# PI_Shield.net
KiCad netlist of a schematic drawn in EAGLE
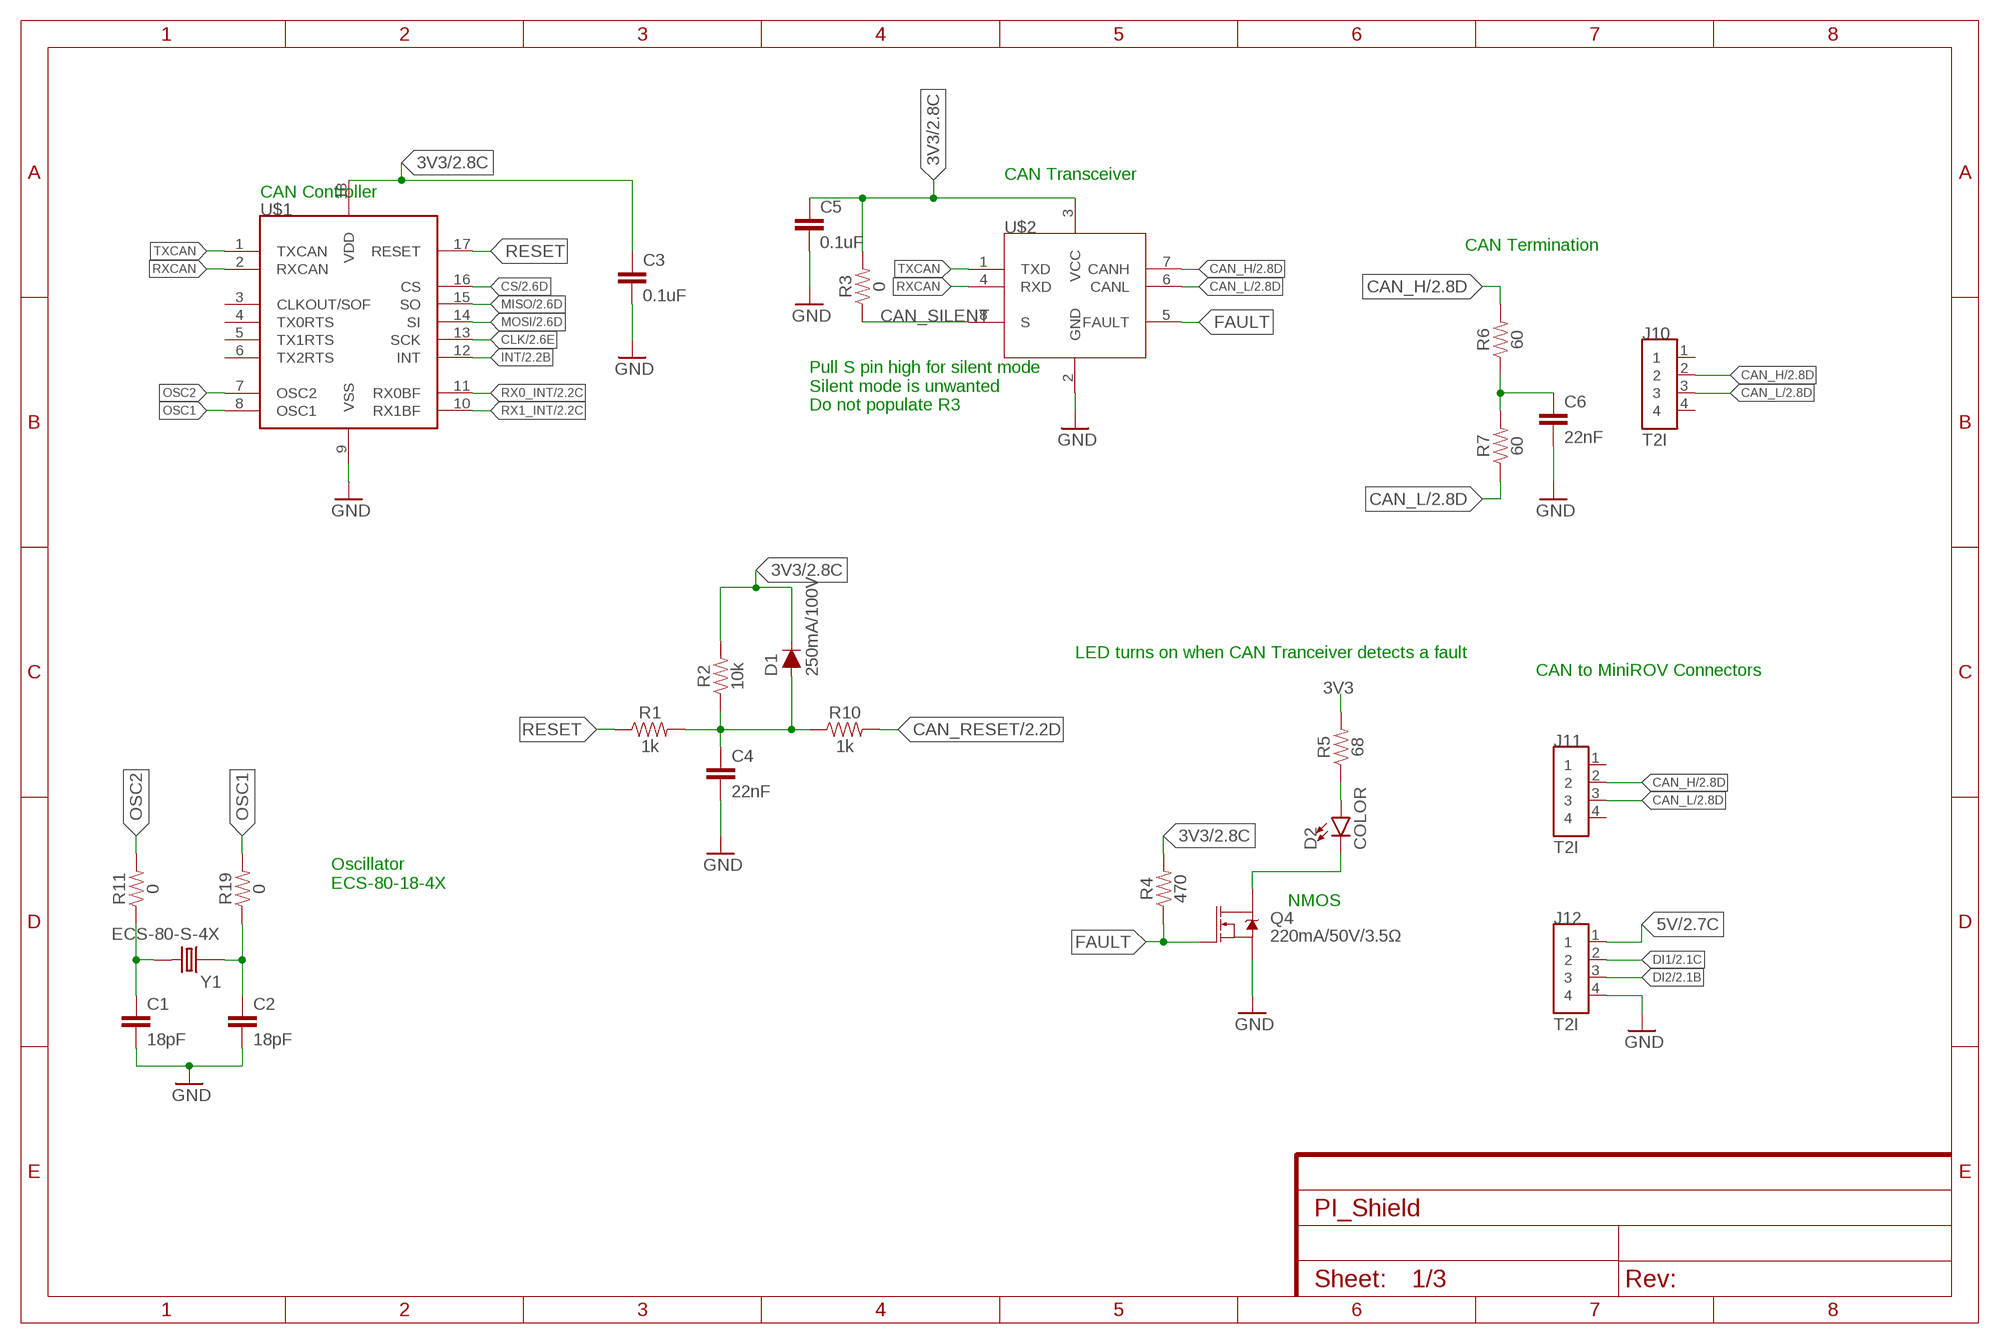
[diagram p0: schematic, sheet 1]
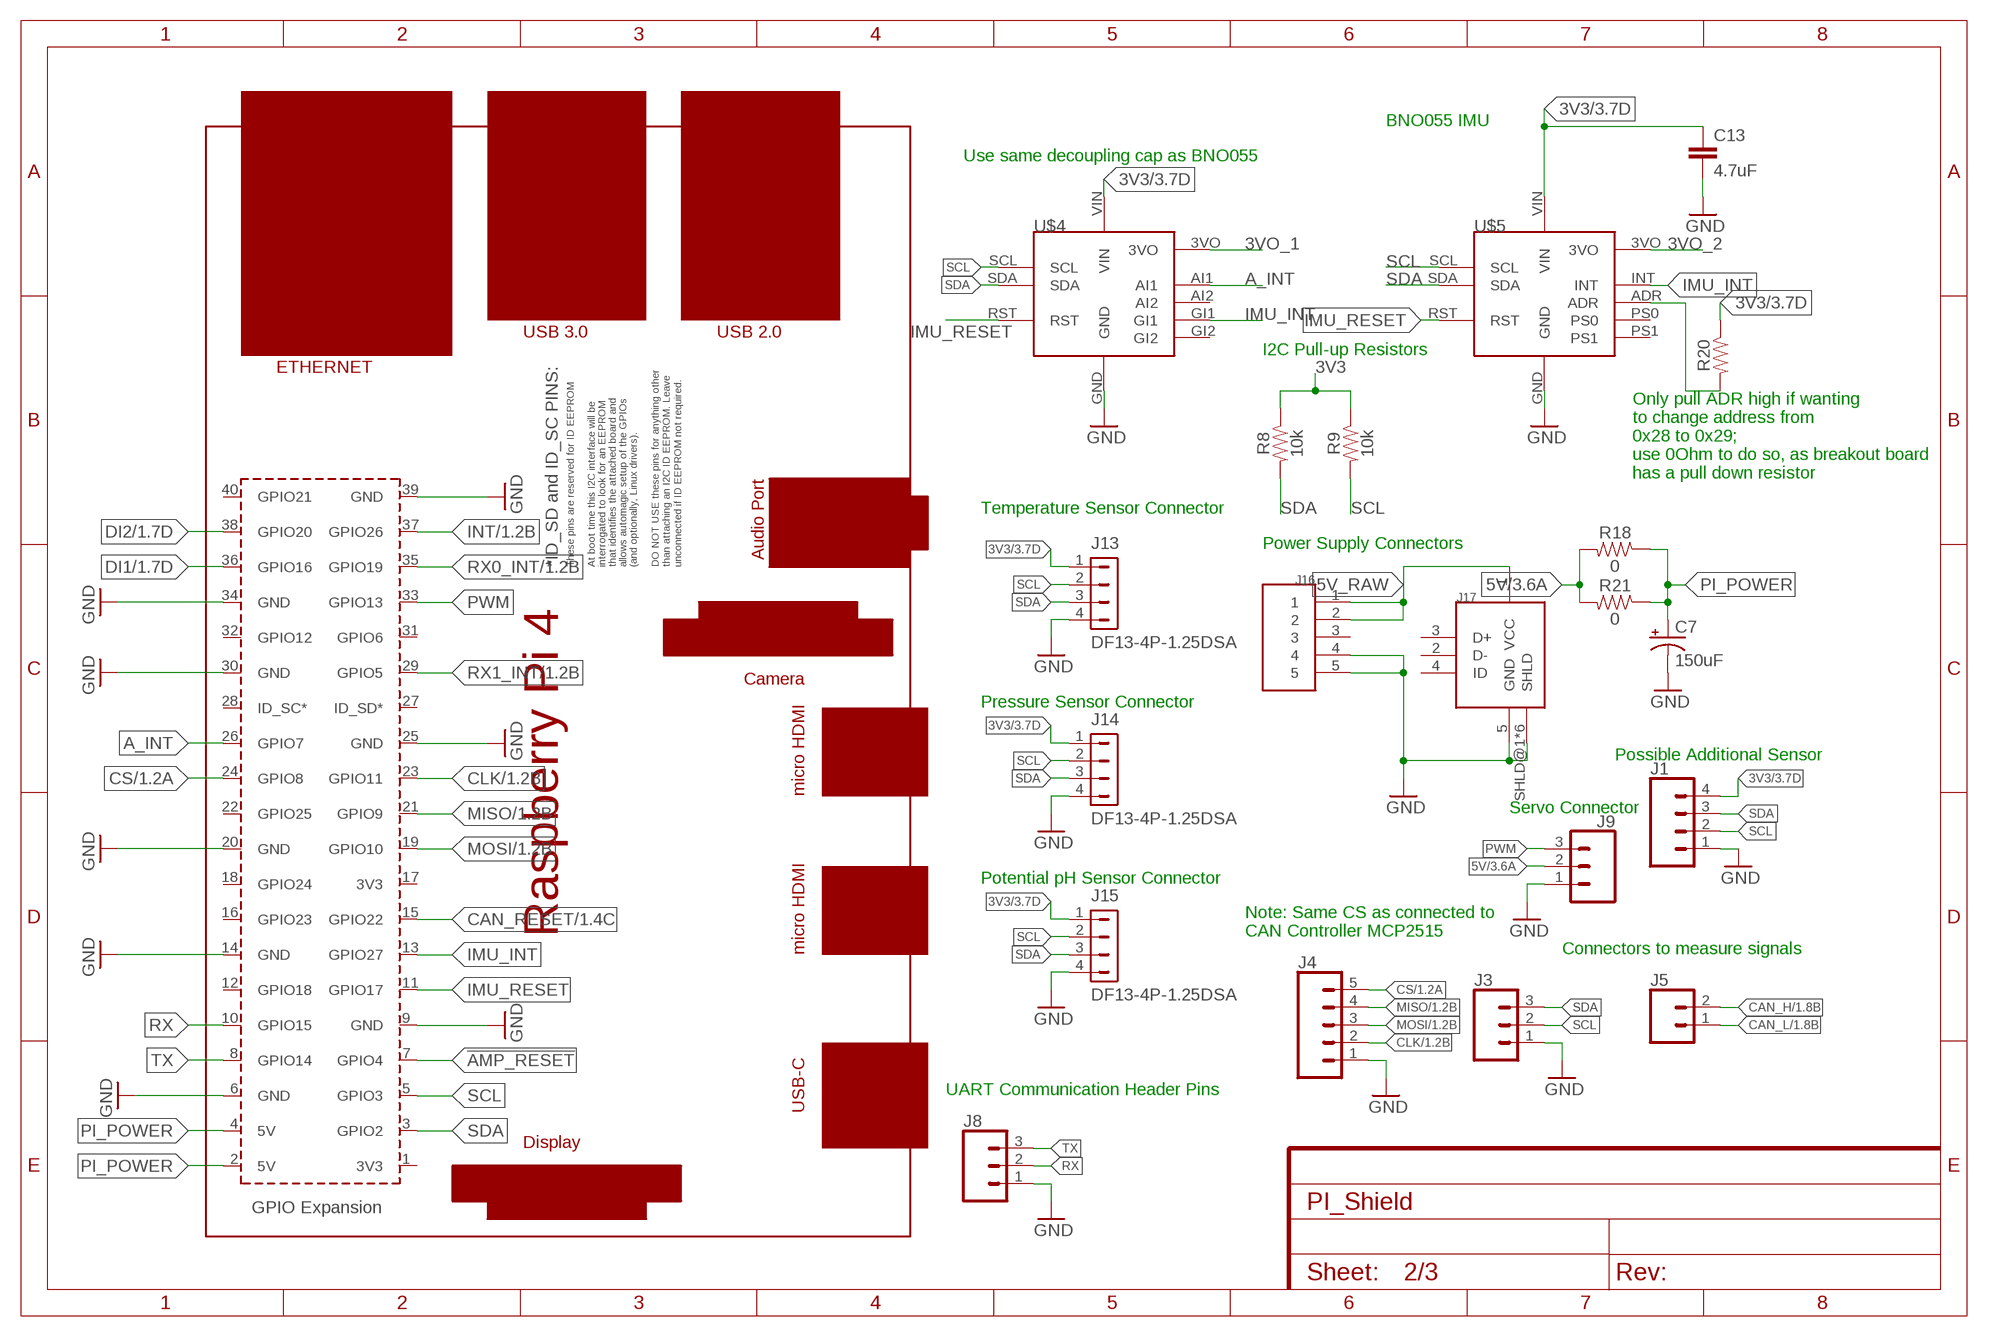
[diagram p1: schematic, sheet 2]
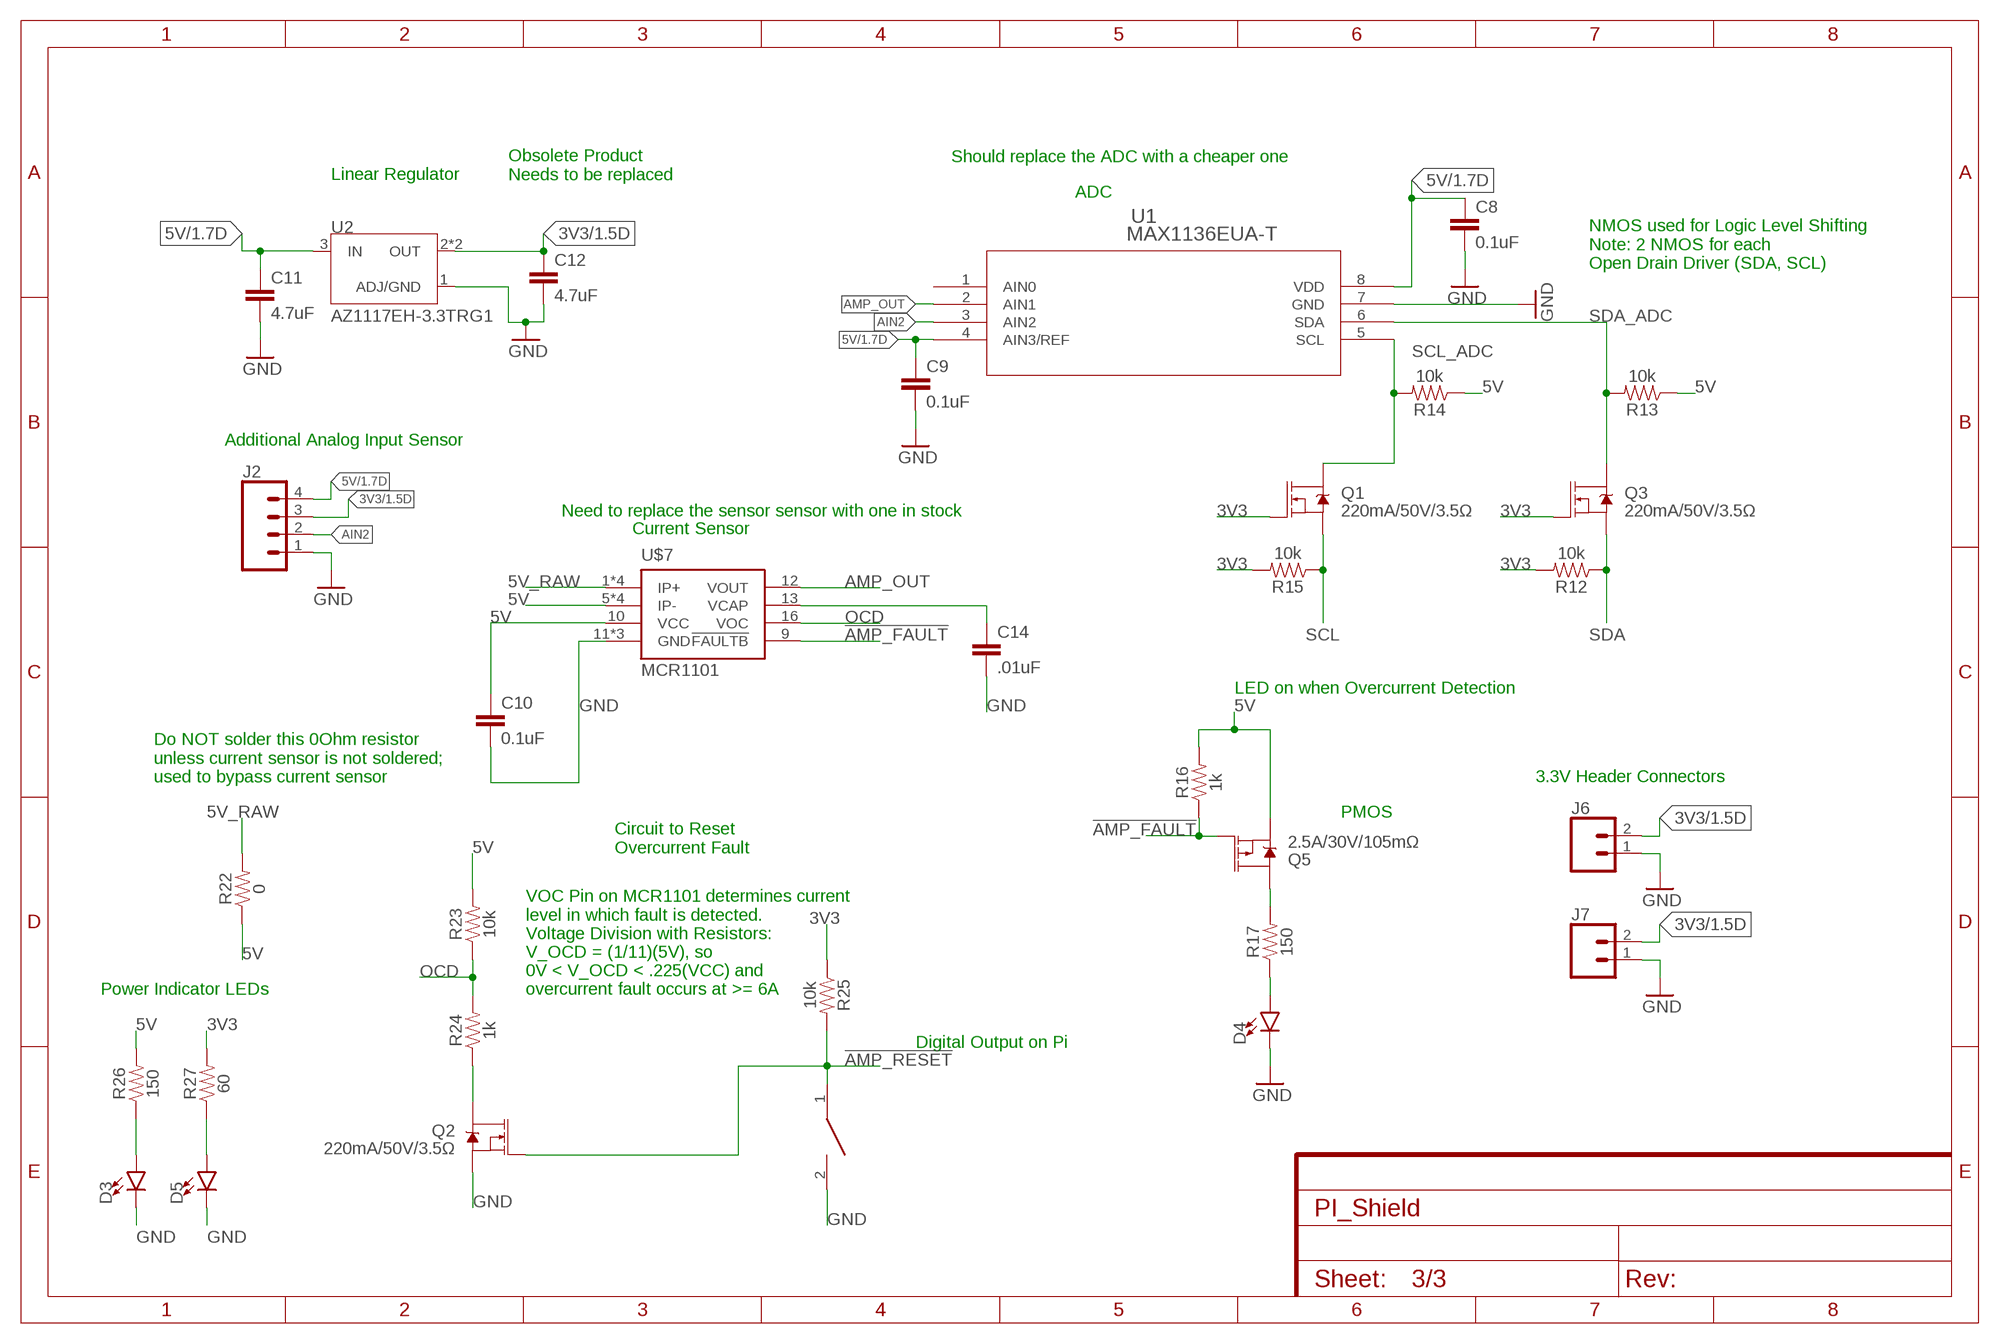
[diagram p2: schematic, sheet 3]

(export (version "E")
  (design (tool "Eeschema 10.0.6"))
  (components
    (comp (ref "C1")
      (value "18pF")
      (footprint "eagle-import:0603")
      (libsource (lib "eagle-import") (part "18PF-0603-50V-5%"))
    )
    (comp (ref "C2")
      (value "18pF")
      (footprint "eagle-import:0603")
      (libsource (lib "eagle-import") (part "18PF-0603-50V-5%"))
    )
    (comp (ref "C3")
      (value "0.1uF")
      (footprint "eagle-import:0603")
      (libsource (lib "eagle-import") (part "22NF/22,000PF-0603-50V-10%"))
    )
    (comp (ref "C4")
      (value "22nF")
      (footprint "eagle-import:0603")
      (libsource (lib "eagle-import") (part "22NF/22,000PF-0603-50V-10%"))
    )
    (comp (ref "C5")
      (value "0.1uF")
      (footprint "eagle-import:0603")
      (libsource (lib "eagle-import") (part "22NF/22,000PF-0603-50V-10%"))
    )
    (comp (ref "C6")
      (value "22nF")
      (footprint "eagle-import:0603")
      (libsource (lib "eagle-import") (part "22NF/22,000PF-0603-50V-10%"))
    )
    (comp (ref "D1")
      (value "250mA/100V")
      (footprint "eagle-import:SOD-323")
      (libsource (lib "eagle-import") (part "DIODE-BAS16J"))
    )
    (comp (ref "D2")
      (value "COLOR")
      (footprint "eagle-import:0805")
      (libsource (lib "eagle-import") (part "LED-0805"))
    )
    (comp (ref "J10")
      (value "T2I")
      (footprint "eagle-import:T2I")
      (libsource (lib "eagle-import") (part "T2I"))
    )
    (comp (ref "J11")
      (value "T2I")
      (footprint "eagle-import:T2I")
      (libsource (lib "eagle-import") (part "T2I"))
    )
    (comp (ref "J12")
      (value "T2I")
      (footprint "eagle-import:T2I")
      (libsource (lib "eagle-import") (part "T2I"))
    )
    (comp (ref "Q4")
      (value "220mA/50V/3.5Ω")
      (footprint "eagle-import:SOT23-3")
      (libsource (lib "eagle-import") (part "MOSFET-NCH-BSS138"))
    )
    (comp (ref "R1")
      (value "1k")
      (footprint "eagle-import:0603")
      (libsource (lib "eagle-import") (part "RESISTOR0603"))
    )
    (comp (ref "R2")
      (value "10k")
      (footprint "eagle-import:0603")
      (libsource (lib "eagle-import") (part "RESISTOR0603"))
    )
    (comp (ref "R3")
      (value "0")
      (footprint "eagle-import:0603")
      (libsource (lib "eagle-import") (part "RESISTOR0603"))
    )
    (comp (ref "R4")
      (value "470")
      (footprint "eagle-import:0603")
      (libsource (lib "eagle-import") (part "RESISTOR0603"))
    )
    (comp (ref "R5")
      (value "68")
      (footprint "eagle-import:0603")
      (libsource (lib "eagle-import") (part "RESISTOR0603"))
    )
    (comp (ref "R6")
      (value "60")
      (footprint "eagle-import:0603")
      (libsource (lib "eagle-import") (part "RESISTOR0603"))
    )
    (comp (ref "R7")
      (value "60")
      (footprint "eagle-import:0603")
      (libsource (lib "eagle-import") (part "RESISTOR0603"))
    )
    (comp (ref "R10")
      (value "1k")
      (footprint "eagle-import:0603")
      (libsource (lib "eagle-import") (part "RESISTOR0603"))
    )
    (comp (ref "R11")
      (value "0")
      (footprint "eagle-import:0603")
      (libsource (lib "eagle-import") (part "RESISTOR0603"))
    )
    (comp (ref "R19")
      (value "0")
      (footprint "eagle-import:0603")
      (libsource (lib "eagle-import") (part "RESISTOR0603"))
    )
    (comp (ref "U$1")
      (value "MCP2515")
      (footprint "eagle-import:SOIC-18")
      (libsource (lib "eagle-import") (part "MCP2515"))
    )
    (comp (ref "U$2")
      (value "TCAN337D")
      (footprint "eagle-import:SOIC-8")
      (libsource (lib "eagle-import") (part "TCAN337D"))
    )
    (comp (ref "Y1")
      (value "ECS-80-S-4X")
      (footprint "eagle-import:XTAL_ECS-80-S-4X")
      (fields (field (name "DIGI-KEY_PART_NUMBER") "X1057-ND") (field (name "MF") "ECS International"))
      (libsource (lib "eagle-import") (part "ECS-80-S-4X"))
    )
    (comp (ref "C8")
      (value "0.1uF")
      (footprint "eagle-import:0603")
      (libsource (lib "eagle-import") (part "22NF/22,000PF-0603-50V-10%"))
    )
    (comp (ref "C9")
      (value "0.1uF")
      (footprint "eagle-import:0603")
      (libsource (lib "eagle-import") (part "22NF/22,000PF-0603-50V-10%"))
    )
    (comp (ref "C10")
      (value "0.1uF")
      (footprint "eagle-import:0603")
      (libsource (lib "eagle-import") (part "22NF/22,000PF-0603-50V-10%"))
    )
    (comp (ref "C11")
      (value "4.7uF")
      (footprint "eagle-import:0603")
      (libsource (lib "eagle-import") (part "22NF/22,000PF-0603-50V-10%"))
    )
    (comp (ref "C12")
      (value "4.7uF")
      (footprint "eagle-import:0603")
      (libsource (lib "eagle-import") (part "22NF/22,000PF-0603-50V-10%"))
    )
    (comp (ref "C14")
      (value ".01uF")
      (footprint "eagle-import:0603")
      (libsource (lib "eagle-import") (part "22NF/22,000PF-0603-50V-10%"))
    )
    (comp (ref "D3")
      (value "LED0603")
      (footprint "eagle-import:LED-0603")
      (libsource (lib "eagle-import") (part "LED0603"))
    )
    (comp (ref "D4")
      (value "LED0603")
      (footprint "eagle-import:LED-0603")
      (libsource (lib "eagle-import") (part "LED0603"))
    )
    (comp (ref "D5")
      (value "LED0603")
      (footprint "eagle-import:LED-0603")
      (libsource (lib "eagle-import") (part "LED0603"))
    )
    (comp (ref "J2")
      (value "CONN_04")
      (footprint "eagle-import:1X04")
      (libsource (lib "eagle-import") (part "CONN_04"))
    )
    (comp (ref "J6")
      (value "CONN_02")
      (footprint "eagle-import:1X02")
      (libsource (lib "eagle-import") (part "CONN_02"))
    )
    (comp (ref "J7")
      (value "CONN_02")
      (footprint "eagle-import:1X02")
      (libsource (lib "eagle-import") (part "CONN_02"))
    )
    (comp (ref "Q1")
      (value "220mA/50V/3.5Ω")
      (footprint "eagle-import:SOT23-3")
      (libsource (lib "eagle-import") (part "MOSFET-NCH-BSS138"))
    )
    (comp (ref "Q2")
      (value "220mA/50V/3.5Ω")
      (footprint "eagle-import:SOT23-3")
      (libsource (lib "eagle-import") (part "MOSFET-NCH-BSS138"))
    )
    (comp (ref "Q3")
      (value "220mA/50V/3.5Ω")
      (footprint "eagle-import:SOT23-3")
      (libsource (lib "eagle-import") (part "MOSFET-NCH-BSS138"))
    )
    (comp (ref "Q5")
      (value "2.5A/30V/105mΩ")
      (footprint "eagle-import:SOT23-3")
      (libsource (lib "eagle-import") (part "MOSFET_PCH-DMG2307L"))
    )
    (comp (ref "R12")
      (value "10k")
      (footprint "eagle-import:0603")
      (libsource (lib "eagle-import") (part "RESISTOR0603"))
    )
    (comp (ref "R13")
      (value "10k")
      (footprint "eagle-import:0603")
      (libsource (lib "eagle-import") (part "RESISTOR0603"))
    )
    (comp (ref "R14")
      (value "10k")
      (footprint "eagle-import:0603")
      (libsource (lib "eagle-import") (part "RESISTOR0603"))
    )
    (comp (ref "R15")
      (value "10k")
      (footprint "eagle-import:0603")
      (libsource (lib "eagle-import") (part "RESISTOR0603"))
    )
    (comp (ref "R16")
      (value "1k")
      (footprint "eagle-import:0603")
      (libsource (lib "eagle-import") (part "RESISTOR0603"))
    )
    (comp (ref "R17")
      (value "150")
      (footprint "eagle-import:0603")
      (libsource (lib "eagle-import") (part "RESISTOR0603"))
    )
    (comp (ref "R22")
      (value "0")
      (footprint "eagle-import:0603")
      (libsource (lib "eagle-import") (part "RESISTOR0603"))
    )
    (comp (ref "R23")
      (value "10k")
      (footprint "eagle-import:0603")
      (libsource (lib "eagle-import") (part "RESISTOR0603"))
    )
    (comp (ref "R24")
      (value "1k")
      (footprint "eagle-import:0603")
      (libsource (lib "eagle-import") (part "RESISTOR0603"))
    )
    (comp (ref "R25")
      (value "10k")
      (footprint "eagle-import:0603")
      (libsource (lib "eagle-import") (part "RESISTOR0603"))
    )
    (comp (ref "R26")
      (value "150")
      (footprint "eagle-import:0603")
      (libsource (lib "eagle-import") (part "RESISTOR0603"))
    )
    (comp (ref "R27")
      (value "60")
      (footprint "eagle-import:0603")
      (libsource (lib "eagle-import") (part "RESISTOR0603"))
    )
    (comp (ref "U$6")
      (value "DISCRETECOMPONENTS_SWITCH")
      (footprint "eagle-import:DISCRETECOMPONENTS_SW_2512")
      (libsource (lib "eagle-import") (part "DISCRETECOMPONENTS_SWITCH"))
    )
    (comp (ref "U$7")
      (value "MCR1101")
      (footprint "eagle-import:SOIC-16")
      (libsource (lib "eagle-import") (part "MCR1101"))
    )
    (comp (ref "U1")
      (value "MAX1136EUA-T")
      (footprint "eagle-import:21-0036K")
      (fields
        (field (name "DIGI-KEY_PART_NUMBER") "MAX1136EUA+-ND")
        (field (name "MF") "Maxim Integrated")
        (field (name "MP") "MAX1136EUA+")
      )
      (libsource (lib "eagle-import") (part "MAX1136EUA-T"))
    )
    (comp (ref "U2")
      (value "AZ1117EH-3.3TRG1")
      (footprint "eagle-import:SOT230P700X180-4N")
      (fields (field (name "MF") "Diodes Inc."))
      (libsource (lib "eagle-import") (part "AZ1117EH-3.3TRG1"))
    )
    (comp (ref "C7")
      (value "150uF")
      (footprint "eagle-import:2917(7343-31-METRIC)")
      (libsource (lib "eagle-import") (part "C-TANTALUM(10UF_150UF)"))
    )
    (comp (ref "C13")
      (value "4.7uF")
      (footprint "eagle-import:0603")
      (libsource (lib "eagle-import") (part "22NF/22,000PF-0603-50V-10%"))
    )
    (comp (ref "J1")
      (value "CONN_04")
      (footprint "eagle-import:1X04")
      (libsource (lib "eagle-import") (part "CONN_04"))
    )
    (comp (ref "J3")
      (value "CONN_03")
      (footprint "eagle-import:1X03")
      (libsource (lib "eagle-import") (part "CONN_03"))
    )
    (comp (ref "J4")
      (value "CONN_05")
      (footprint "eagle-import:1X05")
      (libsource (lib "eagle-import") (part "CONN_05"))
    )
    (comp (ref "J5")
      (value "CONN_02")
      (footprint "eagle-import:1X02")
      (libsource (lib "eagle-import") (part "SparkFun-Connectors_513_CONN_02"))
    )
    (comp (ref "J8")
      (value "CONN_03")
      (footprint "eagle-import:1X03")
      (libsource (lib "eagle-import") (part "CONN_03"))
    )
    (comp (ref "J9")
      (value "CONN_03")
      (footprint "eagle-import:1X03")
      (libsource (lib "eagle-import") (part "CONN_03"))
    )
    (comp (ref "J13")
      (value "DF13-4P-1.25DSA")
      (footprint "eagle-import:DF13-4P-1.25DSA")
      (libsource (lib "eagle-import") (part "DF13-4P-1.25DSA"))
    )
    (comp (ref "J14")
      (value "DF13-4P-1.25DSA")
      (footprint "eagle-import:DF13-4P-1.25DSA")
      (libsource (lib "eagle-import") (part "DF13-4P-1.25DSA"))
    )
    (comp (ref "J15")
      (value "DF13-4P-1.25DSA")
      (footprint "eagle-import:DF13-4P-1.25DSA")
      (libsource (lib "eagle-import") (part "DF13-4P-1.25DSA"))
    )
    (comp (ref "J16")
      (value "T2I5P")
      (footprint "eagle-import:T2I5P")
      (libsource (lib "eagle-import") (part "T2I5P"))
    )
    (comp (ref "J17")
      (value "USB-MICRO")
      (footprint "eagle-import:MICRO-USB")
      (libsource (lib "eagle-import") (part "USB-MICRO"))
    )
    (comp (ref "R8")
      (value "10k")
      (footprint "eagle-import:0603")
      (libsource (lib "eagle-import") (part "RESISTOR0603"))
    )
    (comp (ref "R9")
      (value "10k")
      (footprint "eagle-import:0603")
      (libsource (lib "eagle-import") (part "RESISTOR0603"))
    )
    (comp (ref "R18")
      (value "0")
      (footprint "eagle-import:0603")
      (libsource (lib "eagle-import") (part "RESISTOR0603"))
    )
    (comp (ref "R20")
      (value "RESISTOR0603")
      (footprint "eagle-import:0603")
      (libsource (lib "eagle-import") (part "RESISTOR0603"))
    )
    (comp (ref "R21")
      (value "0")
      (footprint "eagle-import:0603")
      (libsource (lib "eagle-import") (part "RESISTOR0603"))
    )
    (comp (ref "U$4")
      (value "ADAFRUIT-FXOS8700-FXAS21002")
      (footprint "eagle-import:ADAFRUIT-FXOS8700-FXAS21002")
      (libsource (lib "eagle-import") (part "ADAFRUIT-FXOS8700-FXAS21002"))
    )
    (comp (ref "U$5")
      (value "ADAFRUIT-BNO055")
      (footprint "eagle-import:ADAFRUIT-BNO055")
      (libsource (lib "eagle-import") (part "ADAFRUIT-BNO055"))
    )
    (comp (ref "U$8")
      (value "RPI4")
      (footprint "eagle-import:RPI4")
      (libsource (lib "eagle-import") (part "RPI4"))
    )
  )
  (nets
    (net (code "1") (name "3V3") (class "Default")
      (node (ref "C12") (pin "1") (pinfunction "1_1") (pintype "passive"))
      (node (ref "C13") (pin "1") (pinfunction "1_1") (pintype "passive"))
      (node (ref "C3") (pin "1") (pinfunction "1_1") (pintype "passive"))
      (node (ref "C5") (pin "1") (pinfunction "1_1") (pintype "passive"))
      (node (ref "D1") (pin "C") (pinfunction "C_C") (pintype "passive"))
      (node (ref "J1") (pin "4") (pinfunction "4_4") (pintype "passive"))
      (node (ref "J13") (pin "1") (pinfunction "1_1") (pintype "passive"))
      (node (ref "J14") (pin "1") (pinfunction "1_1") (pintype "passive"))
      (node (ref "J15") (pin "1") (pinfunction "1_1") (pintype "passive"))
      (node (ref "J2") (pin "3") (pinfunction "3_3") (pintype "passive"))
      (node (ref "J6") (pin "2") (pinfunction "2_2") (pintype "passive"))
      (node (ref "J7") (pin "2") (pinfunction "2_2") (pintype "passive"))
      (node (ref "Q1") (pin "1") (pinfunction "G_1") (pintype "bidirectional"))
      (node (ref "Q3") (pin "1") (pinfunction "G_1") (pintype "bidirectional"))
      (node (ref "R12") (pin "2") (pinfunction "2_2") (pintype "passive"))
      (node (ref "R15") (pin "2") (pinfunction "2_2") (pintype "passive"))
      (node (ref "R2") (pin "2") (pinfunction "2_2") (pintype "passive"))
      (node (ref "R20") (pin "1") (pinfunction "1_1") (pintype "passive"))
      (node (ref "R25") (pin "1") (pinfunction "1_1") (pintype "passive"))
      (node (ref "R27") (pin "2") (pinfunction "2_2") (pintype "passive"))
      (node (ref "R3") (pin "2") (pinfunction "2_2") (pintype "passive"))
      (node (ref "R4") (pin "2") (pinfunction "2_2") (pintype "passive"))
      (node (ref "R5") (pin "2") (pinfunction "2_2") (pintype "passive"))
      (node (ref "R8") (pin "1") (pinfunction "1_1") (pintype "passive"))
      (node (ref "R9") (pin "1") (pinfunction "1_1") (pintype "passive"))
      (node (ref "U$1") (pin "18") (pinfunction "VDD_18") (pintype "bidirectional"))
      (node (ref "U$2") (pin "3") (pinfunction "VCC_3") (pintype "bidirectional"))
      (node (ref "U$4") (pin "VIN") (pinfunction "VIN_VIN") (pintype "power_in"))
      (node (ref "U$5") (pin "VIN") (pinfunction "VIN_VIN") (pintype "power_in"))
      (node (ref "U2") (pin "2") (pinfunction "OUT_2") (pintype "output"))
      (node (ref "U2") (pin "4") (pinfunction "OUT_4") (pintype "output"))
    )
    (net (code "2") (name "3VO_1") (class "Default")
      (node (ref "U$4") (pin "3VO") (pinfunction "3VO_3VO") (pintype "power_in"))
    )
    (net (code "3") (name "3VO_2") (class "Default")
      (node (ref "U$5") (pin "3VO") (pinfunction "3VO_3VO") (pintype "power_in"))
    )
    (net (code "4") (name "5V") (class "Default")
      (node (ref "C10") (pin "1") (pinfunction "1_1") (pintype "passive"))
      (node (ref "C11") (pin "1") (pinfunction "1_1") (pintype "passive"))
      (node (ref "C8") (pin "1") (pinfunction "1_1") (pintype "passive"))
      (node (ref "C9") (pin "1") (pinfunction "1_1") (pintype "passive"))
      (node (ref "J12") (pin "1") (pinfunction "1_1") (pintype "bidirectional"))
      (node (ref "J2") (pin "4") (pinfunction "4_4") (pintype "passive"))
      (node (ref "J9") (pin "2") (pinfunction "2_2") (pintype "passive"))
      (node (ref "Q5") (pin "2") (pinfunction "S_2") (pintype "bidirectional"))
      (node (ref "R13") (pin "1") (pinfunction "1_1") (pintype "passive"))
      (node (ref "R14") (pin "1") (pinfunction "1_1") (pintype "passive"))
      (node (ref "R16") (pin "2") (pinfunction "2_2") (pintype "passive"))
      (node (ref "R18") (pin "2") (pinfunction "2_2") (pintype "passive"))
      (node (ref "R21") (pin "2") (pinfunction "2_2") (pintype "passive"))
      (node (ref "R22") (pin "1") (pinfunction "1_1") (pintype "passive"))
      (node (ref "R23") (pin "2") (pinfunction "2_2") (pintype "passive"))
      (node (ref "R26") (pin "2") (pinfunction "2_2") (pintype "passive"))
      (node (ref "U$7") (pin "10") (pinfunction "VCC_10") (pintype "bidirectional"))
      (node (ref "U$7") (pin "5") (pinfunction "IP-_5") (pintype "bidirectional"))
      (node (ref "U$7") (pin "6") (pinfunction "IP-_6") (pintype "bidirectional"))
      (node (ref "U$7") (pin "7") (pinfunction "IP-_7") (pintype "bidirectional"))
      (node (ref "U$7") (pin "8") (pinfunction "IP-_8") (pintype "bidirectional"))
      (node (ref "U1") (pin "4") (pinfunction "AIN3/REF_4") (pintype "bidirectional"))
      (node (ref "U1") (pin "8") (pinfunction "VDD_8") (pintype "power_in"))
      (node (ref "U2") (pin "3") (pinfunction "IN_3") (pintype "input"))
    )
    (net (code "5") (name "5V_RAW") (class "Default")
      (node (ref "J16") (pin "1") (pinfunction "1_1") (pintype "bidirectional"))
      (node (ref "J16") (pin "2") (pinfunction "2_2") (pintype "bidirectional"))
      (node (ref "J17") (pin "1") (pinfunction "VCC_1") (pintype "bidirectional"))
      (node (ref "R22") (pin "2") (pinfunction "2_2") (pintype "passive"))
      (node (ref "U$7") (pin "1") (pinfunction "IP+_1") (pintype "bidirectional"))
      (node (ref "U$7") (pin "2") (pinfunction "IP+_2") (pintype "bidirectional"))
      (node (ref "U$7") (pin "3") (pinfunction "IP+_3") (pintype "bidirectional"))
      (node (ref "U$7") (pin "4") (pinfunction "IP+_4") (pintype "bidirectional"))
    )
    (net (code "6") (name "AIN2") (class "Default")
      (node (ref "J2") (pin "2") (pinfunction "2_2") (pintype "passive"))
      (node (ref "U1") (pin "3") (pinfunction "AIN2_3") (pintype "bidirectional"))
    )
    (net (code "7") (name "AMP_OUT") (class "Default")
      (node (ref "U$7") (pin "12") (pinfunction "VOUT_12") (pintype "bidirectional"))
      (node (ref "U1") (pin "2") (pinfunction "AIN1_2") (pintype "bidirectional"))
    )
    (net (code "8") (name "A_INT") (class "Default")
      (node (ref "U$4") (pin "AI1") (pinfunction "AI1_AI1") (pintype "output"))
      (node (ref "U$8") (pin "26") (pinfunction "GPIO7_26") (pintype "bidirectional"))
    )
    (net (code "9") (name "CAN_H") (class "Default")
      (node (ref "J10") (pin "2") (pinfunction "2_2") (pintype "bidirectional"))
      (node (ref "J11") (pin "2") (pinfunction "2_2") (pintype "bidirectional"))
      (node (ref "J5") (pin "2") (pinfunction "2_2") (pintype "passive"))
      (node (ref "R6") (pin "2") (pinfunction "2_2") (pintype "passive"))
      (node (ref "U$2") (pin "7") (pinfunction "CANH_7") (pintype "bidirectional"))
    )
    (net (code "10") (name "CAN_L") (class "Default")
      (node (ref "J10") (pin "3") (pinfunction "3_3") (pintype "bidirectional"))
      (node (ref "J11") (pin "3") (pinfunction "3_3") (pintype "bidirectional"))
      (node (ref "J5") (pin "1") (pinfunction "1_1") (pintype "passive"))
      (node (ref "R7") (pin "1") (pinfunction "1_1") (pintype "passive"))
      (node (ref "U$2") (pin "6") (pinfunction "CANL_6") (pintype "bidirectional"))
    )
    (net (code "11") (name "CAN_RESET") (class "Default")
      (node (ref "R10") (pin "2") (pinfunction "2_2") (pintype "passive"))
      (node (ref "U$8") (pin "15") (pinfunction "GPIO22_15") (pintype "bidirectional"))
    )
    (net (code "12") (name "CAN_SILENT") (class "Default")
      (node (ref "R3") (pin "1") (pinfunction "1_1") (pintype "passive"))
      (node (ref "U$2") (pin "8") (pinfunction "S_8") (pintype "bidirectional"))
    )
    (net (code "13") (name "CLK") (class "Default")
      (node (ref "J4") (pin "2") (pinfunction "2_2") (pintype "passive"))
      (node (ref "U$1") (pin "13") (pinfunction "SCK_13") (pintype "bidirectional"))
      (node (ref "U$8") (pin "23") (pinfunction "GPIO11_23") (pintype "bidirectional"))
    )
    (net (code "14") (name "CS") (class "Default")
      (node (ref "J4") (pin "5") (pinfunction "5_5") (pintype "passive"))
      (node (ref "U$1") (pin "16") (pinfunction "CS_16") (pintype "bidirectional"))
      (node (ref "U$8") (pin "24") (pinfunction "GPIO8_24") (pintype "bidirectional"))
    )
    (net (code "15") (name "DI1") (class "Default")
      (node (ref "J12") (pin "2") (pinfunction "2_2") (pintype "bidirectional"))
      (node (ref "U$8") (pin "36") (pinfunction "GPIO16_36") (pintype "bidirectional"))
    )
    (net (code "16") (name "DI2") (class "Default")
      (node (ref "J12") (pin "3") (pinfunction "3_3") (pintype "bidirectional"))
      (node (ref "U$8") (pin "38") (pinfunction "GPIO20_38") (pintype "bidirectional"))
    )
    (net (code "17") (name "FAULT") (class "Default")
      (node (ref "Q4") (pin "1") (pinfunction "G_1") (pintype "bidirectional"))
      (node (ref "R4") (pin "1") (pinfunction "1_1") (pintype "passive"))
      (node (ref "U$2") (pin "5") (pinfunction "FAULT_5") (pintype "bidirectional"))
    )
    (net (code "18") (name "GND") (class "Default")
      (node (ref "C1") (pin "2") (pinfunction "2_2") (pintype "passive"))
      (node (ref "C10") (pin "2") (pinfunction "2_2") (pintype "passive"))
      (node (ref "C11") (pin "2") (pinfunction "2_2") (pintype "passive"))
      (node (ref "C12") (pin "2") (pinfunction "2_2") (pintype "passive"))
      (node (ref "C13") (pin "2") (pinfunction "2_2") (pintype "passive"))
      (node (ref "C14") (pin "2") (pinfunction "2_2") (pintype "passive"))
      (node (ref "C2") (pin "2") (pinfunction "2_2") (pintype "passive"))
      (node (ref "C3") (pin "2") (pinfunction "2_2") (pintype "passive"))
      (node (ref "C4") (pin "2") (pinfunction "2_2") (pintype "passive"))
      (node (ref "C5") (pin "2") (pinfunction "2_2") (pintype "passive"))
      (node (ref "C6") (pin "2") (pinfunction "2_2") (pintype "passive"))
      (node (ref "C7") (pin "-") (pinfunction "-_-") (pintype "passive"))
      (node (ref "C8") (pin "2") (pinfunction "2_2") (pintype "passive"))
      (node (ref "C9") (pin "2") (pinfunction "2_2") (pintype "passive"))
      (node (ref "D3") (pin "C") (pinfunction "C_C") (pintype "passive"))
      (node (ref "D4") (pin "C") (pinfunction "C_C") (pintype "passive"))
      (node (ref "D5") (pin "C") (pinfunction "C_C") (pintype "passive"))
      (node (ref "J1") (pin "1") (pinfunction "1_1") (pintype "passive"))
      (node (ref "J12") (pin "4") (pinfunction "4_4") (pintype "bidirectional"))
      (node (ref "J13") (pin "4") (pinfunction "4_4") (pintype "passive"))
      (node (ref "J14") (pin "4") (pinfunction "4_4") (pintype "passive"))
      (node (ref "J15") (pin "4") (pinfunction "4_4") (pintype "passive"))
      (node (ref "J16") (pin "4") (pinfunction "4_4") (pintype "bidirectional"))
      (node (ref "J16") (pin "5") (pinfunction "5_5") (pintype "bidirectional"))
      (node (ref "J17") (pin "5") (pinfunction "GND_5") (pintype "bidirectional"))
      (node (ref "J17") (pin "SHLD@1") (pinfunction "SHLD_SHLD@1") (pintype "bidirectional"))
      (node (ref "J17") (pin "SHLD@2") (pinfunction "SHLD_SHLD@2") (pintype "bidirectional"))
      (node (ref "J17") (pin "SHLD@3") (pinfunction "SHLD_SHLD@3") (pintype "bidirectional"))
      (node (ref "J17") (pin "SHLD@4") (pinfunction "SHLD_SHLD@4") (pintype "bidirectional"))
      (node (ref "J17") (pin "SHLD@5") (pinfunction "SHLD_SHLD@5") (pintype "bidirectional"))
      (node (ref "J17") (pin "SHLD@6") (pinfunction "SHLD_SHLD@6") (pintype "bidirectional"))
      (node (ref "J2") (pin "1") (pinfunction "1_1") (pintype "passive"))
      (node (ref "J3") (pin "1") (pinfunction "1_1") (pintype "passive"))
      (node (ref "J4") (pin "1") (pinfunction "1_1") (pintype "passive"))
      (node (ref "J6") (pin "1") (pinfunction "1_1") (pintype "passive"))
      (node (ref "J7") (pin "1") (pinfunction "1_1") (pintype "passive"))
      (node (ref "J8") (pin "1") (pinfunction "1_1") (pintype "passive"))
      (node (ref "J9") (pin "1") (pinfunction "1_1") (pintype "passive"))
      (node (ref "Q2") (pin "2") (pinfunction "S_2") (pintype "bidirectional"))
      (node (ref "Q4") (pin "2") (pinfunction "S_2") (pintype "bidirectional"))
      (node (ref "U$1") (pin "9") (pinfunction "VSS_9") (pintype "bidirectional"))
      (node (ref "U$2") (pin "2") (pinfunction "GND_2") (pintype "bidirectional"))
      (node (ref "U$4") (pin "GND") (pinfunction "GND_GND") (pintype "power_in"))
      (node (ref "U$5") (pin "GND") (pinfunction "GND_GND") (pintype "power_in"))
      (node (ref "U$6") (pin "2") (pinfunction "P$2_2") (pintype "bidirectional"))
      (node (ref "U$7") (pin "11") (pinfunction "GND_11") (pintype "bidirectional"))
      (node (ref "U$7") (pin "14") (pinfunction "GND_14") (pintype "bidirectional"))
      (node (ref "U$7") (pin "15") (pinfunction "GND_15") (pintype "bidirectional"))
      (node (ref "U$8") (pin "14") (pinfunction "GND_14") (pintype "bidirectional"))
      (node (ref "U$8") (pin "20") (pinfunction "GND_20") (pintype "bidirectional"))
      (node (ref "U$8") (pin "25") (pinfunction "GND_25") (pintype "bidirectional"))
      (node (ref "U$8") (pin "30") (pinfunction "GND_30") (pintype "bidirectional"))
      (node (ref "U$8") (pin "34") (pinfunction "GND_34") (pintype "bidirectional"))
      (node (ref "U$8") (pin "39") (pinfunction "GND_39") (pintype "bidirectional"))
      (node (ref "U$8") (pin "6") (pinfunction "GND_6") (pintype "bidirectional"))
      (node (ref "U$8") (pin "9") (pinfunction "GND_9") (pintype "bidirectional"))
      (node (ref "U1") (pin "7") (pinfunction "GND_7") (pintype "power_in"))
      (node (ref "U2") (pin "1") (pinfunction "ADJ/GND_1") (pintype "power_in"))
    )
    (net (code "19") (name "IMU_INT") (class "Default")
      (node (ref "U$4") (pin "GI1") (pinfunction "GI1_GI1") (pintype "output"))
      (node (ref "U$5") (pin "INT") (pinfunction "INT_INT") (pintype "output"))
      (node (ref "U$8") (pin "13") (pinfunction "GPIO27_13") (pintype "bidirectional"))
    )
    (net (code "20") (name "IMU_RESET") (class "Default")
      (node (ref "U$4") (pin "RST") (pinfunction "RST_RST") (pintype "input"))
      (node (ref "U$5") (pin "RST") (pinfunction "RST_RST") (pintype "input"))
      (node (ref "U$8") (pin "11") (pinfunction "GPIO17_11") (pintype "bidirectional"))
    )
    (net (code "21") (name "INT") (class "Default")
      (node (ref "U$1") (pin "12") (pinfunction "INT_12") (pintype "bidirectional"))
      (node (ref "U$8") (pin "37") (pinfunction "GPIO26_37") (pintype "bidirectional"))
    )
    (net (code "22") (name "MISO") (class "Default")
      (node (ref "J4") (pin "4") (pinfunction "4_4") (pintype "passive"))
      (node (ref "U$1") (pin "15") (pinfunction "SO_15") (pintype "bidirectional"))
      (node (ref "U$8") (pin "21") (pinfunction "GPIO9_21") (pintype "bidirectional"))
    )
    (net (code "23") (name "MOSI") (class "Default")
      (node (ref "J4") (pin "3") (pinfunction "3_3") (pintype "passive"))
      (node (ref "U$1") (pin "14") (pinfunction "SI_14") (pintype "bidirectional"))
      (node (ref "U$8") (pin "19") (pinfunction "GPIO10_19") (pintype "bidirectional"))
    )
    (net (code "24") (name "Net-(C1-Pad1)") (class "Default")
      (node (ref "C1") (pin "1") (pinfunction "1_1") (pintype "passive"))
      (node (ref "R11") (pin "1") (pinfunction "1_1") (pintype "passive"))
      (node (ref "Y1") (pin "2") (pinfunction "2_2") (pintype "passive"))
    )
    (net (code "25") (name "Net-(C2-Pad1)") (class "Default")
      (node (ref "C2") (pin "1") (pinfunction "1_1") (pintype "passive"))
      (node (ref "R19") (pin "1") (pinfunction "1_1") (pintype "passive"))
      (node (ref "Y1") (pin "1") (pinfunction "1_1") (pintype "passive"))
    )
    (net (code "26") (name "Net-(C4-Pad1)") (class "Default")
      (node (ref "C4") (pin "1") (pinfunction "1_1") (pintype "passive"))
      (node (ref "D1") (pin "A") (pinfunction "A_A") (pintype "passive"))
      (node (ref "R1") (pin "2") (pinfunction "2_2") (pintype "passive"))
      (node (ref "R10") (pin "1") (pinfunction "1_1") (pintype "passive"))
      (node (ref "R2") (pin "1") (pinfunction "1_1") (pintype "passive"))
    )
    (net (code "27") (name "Net-(C6-Pad1)") (class "Default")
      (node (ref "C6") (pin "1") (pinfunction "1_1") (pintype "passive"))
      (node (ref "R6") (pin "1") (pinfunction "1_1") (pintype "passive"))
      (node (ref "R7") (pin "2") (pinfunction "2_2") (pintype "passive"))
    )
    (net (code "28") (name "Net-(D2-PadA)") (class "Default")
      (node (ref "D2") (pin "A") (pinfunction "A_A") (pintype "passive"))
      (node (ref "R5") (pin "1") (pinfunction "1_1") (pintype "passive"))
    )
    (net (code "29") (name "Net-(D3-PadA)") (class "Default")
      (node (ref "D3") (pin "A") (pinfunction "A_A") (pintype "passive"))
      (node (ref "R26") (pin "1") (pinfunction "1_1") (pintype "passive"))
    )
    (net (code "30") (name "Net-(D4-PadA)") (class "Default")
      (node (ref "D4") (pin "A") (pinfunction "A_A") (pintype "passive"))
      (node (ref "R17") (pin "1") (pinfunction "1_1") (pintype "passive"))
    )
    (net (code "31") (name "Net-(D5-PadA)") (class "Default")
      (node (ref "D5") (pin "A") (pinfunction "A_A") (pintype "passive"))
      (node (ref "R27") (pin "1") (pinfunction "1_1") (pintype "passive"))
    )
    (net (code "32") (name "Net-(Q2-D)") (class "Default")
      (node (ref "Q2") (pin "3") (pinfunction "D_3") (pintype "bidirectional"))
      (node (ref "R24") (pin "1") (pinfunction "1_1") (pintype "passive"))
    )
    (net (code "33") (name "Net-(Q4-D)") (class "Default")
      (node (ref "D2") (pin "C") (pinfunction "C_C") (pintype "passive"))
      (node (ref "Q4") (pin "3") (pinfunction "D_3") (pintype "bidirectional"))
    )
    (net (code "34") (name "Net-(Q5-D)") (class "Default")
      (node (ref "Q5") (pin "3") (pinfunction "D_3") (pintype "bidirectional"))
      (node (ref "R17") (pin "2") (pinfunction "2_2") (pintype "passive"))
    )
    (net (code "35") (name "Net-(R20-Pad2)") (class "Default")
      (node (ref "R20") (pin "2") (pinfunction "2_2") (pintype "passive"))
      (node (ref "U$5") (pin "ADR") (pinfunction "ADR_ADR") (pintype "input"))
    )
    (net (code "36") (name "Net-(U$7-VCAP)") (class "Default")
      (node (ref "C14") (pin "1") (pinfunction "1_1") (pintype "passive"))
      (node (ref "U$7") (pin "13") (pinfunction "VCAP_13") (pintype "bidirectional"))
    )
    (net (code "37") (name "OCD") (class "Default")
      (node (ref "R23") (pin "1") (pinfunction "1_1") (pintype "passive"))
      (node (ref "R24") (pin "2") (pinfunction "2_2") (pintype "passive"))
      (node (ref "U$7") (pin "16") (pinfunction "VOC_16") (pintype "bidirectional"))
    )
    (net (code "38") (name "OSC1") (class "Default")
      (node (ref "R19") (pin "2") (pinfunction "2_2") (pintype "passive"))
      (node (ref "U$1") (pin "8") (pinfunction "OSC1_8") (pintype "bidirectional"))
    )
    (net (code "39") (name "OSC2") (class "Default")
      (node (ref "R11") (pin "2") (pinfunction "2_2") (pintype "passive"))
      (node (ref "U$1") (pin "7") (pinfunction "OSC2_7") (pintype "bidirectional"))
    )
    (net (code "40") (name "PI_POWER") (class "Default")
      (node (ref "C7") (pin "+") (pinfunction "+_+") (pintype "passive"))
      (node (ref "R18") (pin "1") (pinfunction "1_1") (pintype "passive"))
      (node (ref "R21") (pin "1") (pinfunction "1_1") (pintype "passive"))
      (node (ref "U$8") (pin "2") (pinfunction "5V_2") (pintype "bidirectional"))
      (node (ref "U$8") (pin "4") (pinfunction "5V_4") (pintype "bidirectional"))
    )
    (net (code "41") (name "PWM") (class "Default")
      (node (ref "J9") (pin "3") (pinfunction "3_3") (pintype "passive"))
      (node (ref "U$8") (pin "33") (pinfunction "GPIO13_33") (pintype "bidirectional"))
    )
    (net (code "42") (name "RESET") (class "Default")
      (node (ref "R1") (pin "1") (pinfunction "1_1") (pintype "passive"))
      (node (ref "U$1") (pin "17") (pinfunction "RESET_17") (pintype "bidirectional"))
    )
    (net (code "43") (name "RX") (class "Default")
      (node (ref "J8") (pin "2") (pinfunction "2_2") (pintype "passive"))
      (node (ref "U$8") (pin "10") (pinfunction "GPIO15_10") (pintype "bidirectional"))
    )
    (net (code "44") (name "RX0_INT") (class "Default")
      (node (ref "U$1") (pin "11") (pinfunction "RX0BF_11") (pintype "bidirectional"))
      (node (ref "U$8") (pin "35") (pinfunction "GPIO19_35") (pintype "bidirectional"))
    )
    (net (code "45") (name "RX1_INT") (class "Default")
      (node (ref "U$1") (pin "10") (pinfunction "RX1BF_10") (pintype "bidirectional"))
      (node (ref "U$8") (pin "29") (pinfunction "GPIO5_29") (pintype "bidirectional"))
    )
    (net (code "46") (name "RXCAN") (class "Default")
      (node (ref "U$1") (pin "2") (pinfunction "RXCAN_2") (pintype "bidirectional"))
      (node (ref "U$2") (pin "4") (pinfunction "RXD_4") (pintype "bidirectional"))
    )
    (net (code "47") (name "SCL") (class "Default")
      (node (ref "J1") (pin "2") (pinfunction "2_2") (pintype "passive"))
      (node (ref "J13") (pin "2") (pinfunction "2_2") (pintype "passive"))
      (node (ref "J14") (pin "2") (pinfunction "2_2") (pintype "passive"))
      (node (ref "J15") (pin "2") (pinfunction "2_2") (pintype "passive"))
      (node (ref "J3") (pin "2") (pinfunction "2_2") (pintype "passive"))
      (node (ref "Q1") (pin "2") (pinfunction "S_2") (pintype "bidirectional"))
      (node (ref "R15") (pin "1") (pinfunction "1_1") (pintype "passive"))
      (node (ref "R9") (pin "2") (pinfunction "2_2") (pintype "passive"))
      (node (ref "U$4") (pin "SCL") (pinfunction "SCL_SCL") (pintype "bidirectional"))
      (node (ref "U$5") (pin "SCL") (pinfunction "SCL_SCL") (pintype "bidirectional"))
      (node (ref "U$8") (pin "5") (pinfunction "GPIO3_5") (pintype "bidirectional"))
    )
    (net (code "48") (name "SCL_ADC") (class "Default")
      (node (ref "Q1") (pin "3") (pinfunction "D_3") (pintype "bidirectional"))
      (node (ref "R14") (pin "2") (pinfunction "2_2") (pintype "passive"))
      (node (ref "U1") (pin "5") (pinfunction "SCL_5") (pintype "bidirectional"))
    )
    (net (code "49") (name "SDA") (class "Default")
      (node (ref "J1") (pin "3") (pinfunction "3_3") (pintype "passive"))
      (node (ref "J13") (pin "3") (pinfunction "3_3") (pintype "passive"))
      (node (ref "J14") (pin "3") (pinfunction "3_3") (pintype "passive"))
      (node (ref "J15") (pin "3") (pinfunction "3_3") (pintype "passive"))
      (node (ref "J3") (pin "3") (pinfunction "3_3") (pintype "passive"))
      (node (ref "Q3") (pin "2") (pinfunction "S_2") (pintype "bidirectional"))
      (node (ref "R12") (pin "1") (pinfunction "1_1") (pintype "passive"))
      (node (ref "R8") (pin "2") (pinfunction "2_2") (pintype "passive"))
      (node (ref "U$4") (pin "SDA") (pinfunction "SDA_SDA") (pintype "bidirectional"))
      (node (ref "U$5") (pin "SDA") (pinfunction "SDA_SDA") (pintype "bidirectional"))
      (node (ref "U$8") (pin "3") (pinfunction "GPIO2_3") (pintype "bidirectional"))
    )
    (net (code "50") (name "SDA_ADC") (class "Default")
      (node (ref "Q3") (pin "3") (pinfunction "D_3") (pintype "bidirectional"))
      (node (ref "R13") (pin "2") (pinfunction "2_2") (pintype "passive"))
      (node (ref "U1") (pin "6") (pinfunction "SDA_6") (pintype "bidirectional"))
    )
    (net (code "51") (name "TX") (class "Default")
      (node (ref "J8") (pin "3") (pinfunction "3_3") (pintype "passive"))
      (node (ref "U$8") (pin "8") (pinfunction "GPIO14_8") (pintype "bidirectional"))
    )
    (net (code "52") (name "TXCAN") (class "Default")
      (node (ref "U$1") (pin "1") (pinfunction "TXCAN_1") (pintype "bidirectional"))
      (node (ref "U$2") (pin "1") (pinfunction "TXD_1") (pintype "bidirectional"))
    )
    (net (code "53") (name "unconnected-(J10-Pad1)") (class "Default")
      (node (ref "J10") (pin "1") (pinfunction "1_1") (pintype "bidirectional"))
    )
    (net (code "54") (name "unconnected-(J10-Pad4)") (class "Default")
      (node (ref "J10") (pin "4") (pinfunction "4_4") (pintype "bidirectional"))
    )
    (net (code "55") (name "unconnected-(J11-Pad1)") (class "Default")
      (node (ref "J11") (pin "1") (pinfunction "1_1") (pintype "bidirectional"))
    )
    (net (code "56") (name "unconnected-(J11-Pad4)") (class "Default")
      (node (ref "J11") (pin "4") (pinfunction "4_4") (pintype "bidirectional"))
    )
    (net (code "57") (name "unconnected-(J16-Pad3)") (class "Default")
      (node (ref "J16") (pin "3") (pinfunction "3_3") (pintype "bidirectional"))
    )
    (net (code "58") (name "unconnected-(J17-D+-Pad3)") (class "Default")
      (node (ref "J17") (pin "3") (pinfunction "D+_3") (pintype "bidirectional"))
    )
    (net (code "59") (name "unconnected-(J17-D--Pad2)") (class "Default")
      (node (ref "J17") (pin "2") (pinfunction "D-_2") (pintype "bidirectional"))
    )
    (net (code "60") (name "unconnected-(J17-ID-Pad4)") (class "Default")
      (node (ref "J17") (pin "4") (pinfunction "ID_4") (pintype "bidirectional"))
    )
    (net (code "61") (name "unconnected-(U$1-CLKOUT{slash}SOF-Pad3)") (class "Default")
      (node (ref "U$1") (pin "3") (pinfunction "CLKOUT/SOF_3") (pintype "bidirectional"))
    )
    (net (code "62") (name "unconnected-(U$1-TX0RTS-Pad4)") (class "Default")
      (node (ref "U$1") (pin "4") (pinfunction "TX0RTS_4") (pintype "bidirectional"))
    )
    (net (code "63") (name "unconnected-(U$1-TX1RTS-Pad5)") (class "Default")
      (node (ref "U$1") (pin "5") (pinfunction "TX1RTS_5") (pintype "bidirectional"))
    )
    (net (code "64") (name "unconnected-(U$1-TX2RTS-Pad6)") (class "Default")
      (node (ref "U$1") (pin "6") (pinfunction "TX2RTS_6") (pintype "bidirectional"))
    )
    (net (code "65") (name "unconnected-(U$4-PadAI2)") (class "Default")
      (node (ref "U$4") (pin "AI2") (pinfunction "AI2_AI2") (pintype "output"))
    )
    (net (code "66") (name "unconnected-(U$4-PadGI2)") (class "Default")
      (node (ref "U$4") (pin "GI2") (pinfunction "GI2_GI2") (pintype "output"))
    )
    (net (code "67") (name "unconnected-(U$5-PadPS0)") (class "Default")
      (node (ref "U$5") (pin "PS0") (pinfunction "PS0_PS0") (pintype "input"))
    )
    (net (code "68") (name "unconnected-(U$5-PadPS1)") (class "Default")
      (node (ref "U$5") (pin "PS1") (pinfunction "PS1_PS1") (pintype "input"))
    )
    (net (code "69") (name "unconnected-(U$8-3V3-Pad1)") (class "Default")
      (node (ref "U$8") (pin "1") (pinfunction "3V3_1") (pintype "bidirectional"))
    )
    (net (code "70") (name "unconnected-(U$8-3V3-Pad17)") (class "Default")
      (node (ref "U$8") (pin "17") (pinfunction "3V3_17") (pintype "bidirectional"))
    )
    (net (code "71") (name "unconnected-(U$8-GPIO6-Pad31)") (class "Default")
      (node (ref "U$8") (pin "31") (pinfunction "GPIO6_31") (pintype "bidirectional"))
    )
    (net (code "72") (name "unconnected-(U$8-GPIO12-Pad32)") (class "Default")
      (node (ref "U$8") (pin "32") (pinfunction "GPIO12_32") (pintype "bidirectional"))
    )
    (net (code "73") (name "unconnected-(U$8-GPIO18-Pad12)") (class "Default")
      (node (ref "U$8") (pin "12") (pinfunction "GPIO18_12") (pintype "bidirectional"))
    )
    (net (code "74") (name "unconnected-(U$8-GPIO21-Pad40)") (class "Default")
      (node (ref "U$8") (pin "40") (pinfunction "GPIO21_40") (pintype "bidirectional"))
    )
    (net (code "75") (name "unconnected-(U$8-GPIO23-Pad16)") (class "Default")
      (node (ref "U$8") (pin "16") (pinfunction "GPIO23_16") (pintype "bidirectional"))
    )
    (net (code "76") (name "unconnected-(U$8-GPIO24-Pad18)") (class "Default")
      (node (ref "U$8") (pin "18") (pinfunction "GPIO24_18") (pintype "bidirectional"))
    )
    (net (code "77") (name "unconnected-(U$8-GPIO25-Pad22)") (class "Default")
      (node (ref "U$8") (pin "22") (pinfunction "GPIO25_22") (pintype "bidirectional"))
    )
    (net (code "78") (name "unconnected-(U$8-ID_SC*-Pad28)") (class "Default")
      (node (ref "U$8") (pin "28") (pinfunction "ID_SC*_28") (pintype "bidirectional"))
    )
    (net (code "79") (name "unconnected-(U$8-ID_SD*-Pad27)") (class "Default")
      (node (ref "U$8") (pin "27") (pinfunction "ID_SD*_27") (pintype "bidirectional"))
    )
    (net (code "80") (name "unconnected-(U1-AIN0-Pad1)") (class "Default")
      (node (ref "U1") (pin "1") (pinfunction "AIN0_1") (pintype "bidirectional"))
    )
    (net (code "81") (name "~{AMP_FAULT}") (class "Default")
      (node (ref "Q5") (pin "1") (pinfunction "G_1") (pintype "bidirectional"))
      (node (ref "R16") (pin "1") (pinfunction "1_1") (pintype "passive"))
      (node (ref "U$7") (pin "9") (pinfunction "~{FAULTB}_9") (pintype "bidirectional"))
    )
    (net (code "82") (name "~{AMP_RESET}") (class "Default")
      (node (ref "Q2") (pin "1") (pinfunction "G_1") (pintype "bidirectional"))
      (node (ref "R25") (pin "2") (pinfunction "2_2") (pintype "passive"))
      (node (ref "U$6") (pin "1") (pinfunction "P$1_1") (pintype "bidirectional"))
      (node (ref "U$8") (pin "7") (pinfunction "GPIO4_7") (pintype "bidirectional"))
    )
  )
)
